# Open_Playback_Recorder_Bottom.net
KiCad netlist of a schematic drawn in EAGLE
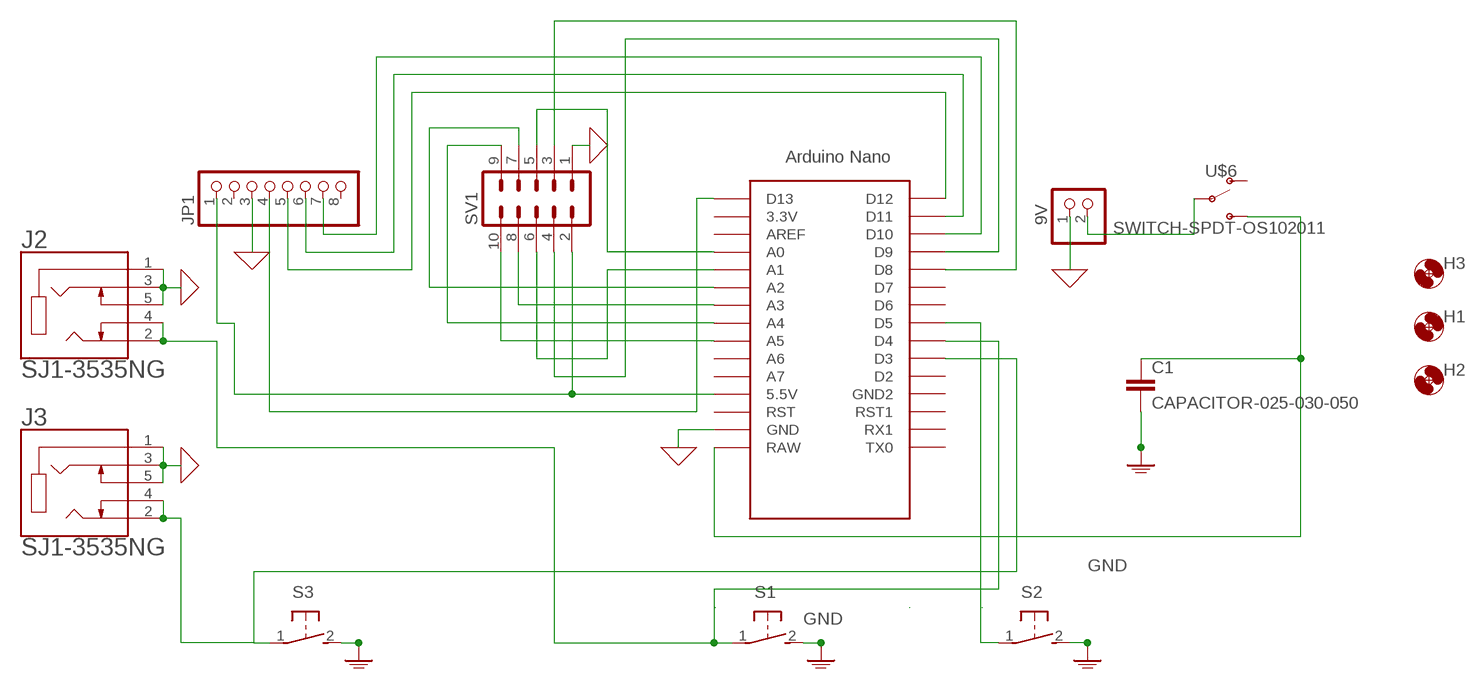
[diagram p0: schematic, sheet 1]

(export (version "E")
  (design (tool "Eeschema 10.0.6"))
  (components
    (comp (ref "9V")
      (value "PINHD-1X2")
      (footprint "eagle-import:1X02")
      (libsource (lib "eagle-import") (part "PINHD-1X2"))
    )
    (comp (ref "C1")
      (value "CAPACITOR-025-030-050")
      (footprint "eagle-import:CAP-025-030X050")
      (libsource (lib "eagle-import") (part "CAPACITOR-025-030-050"))
    )
    (comp (ref "H1")
      (value "MOUNT-HOLE-3MM-CLEAR")
      (footprint "eagle-import:HOLE-3MM-CLEAR")
      (libsource (lib "eagle-import") (part "MOUNT-HOLE-3MM-CLEAR"))
    )
    (comp (ref "H2")
      (value "MOUNT-HOLE-3MM-CLEAR")
      (footprint "eagle-import:HOLE-3MM-CLEAR")
      (libsource (lib "eagle-import") (part "MOUNT-HOLE-3MM-CLEAR"))
    )
    (comp (ref "H3")
      (value "MOUNT-HOLE-3MM-CLEAR")
      (footprint "eagle-import:HOLE-3MM-CLEAR")
      (libsource (lib "eagle-import") (part "MOUNT-HOLE-3MM-CLEAR"))
    )
    (comp (ref "J2")
      (value "SJ1-3535NG")
      (footprint "eagle-import:CUI_SJ1-3535NG")
      (fields (field (name "MANUFACTURER") "CUI"))
      (libsource (lib "eagle-import") (part "SJ1-3535NG"))
    )
    (comp (ref "J3")
      (value "SJ1-3535NG")
      (footprint "eagle-import:CUI_SJ1-3535NG")
      (fields (field (name "MANUFACTURER") "CUI"))
      (libsource (lib "eagle-import") (part "SJ1-3535NG"))
    )
    (comp (ref "JP1")
      (value "HEADER_MALE-1X8ROUND")
      (footprint "eagle-import:1X08_ROUND")
      (libsource (lib "eagle-import") (part "HEADER_MALE-1X8ROUND"))
    )
    (comp (ref "S1")
      (value "SWITCH_OMRON_RA-RA")
      (footprint "eagle-import:B3F-31XX")
      (libsource (lib "eagle-import") (part "SWITCH_OMRON_RA-RA"))
    )
    (comp (ref "S2")
      (value "SWITCH_OMRON_RA-RA")
      (footprint "eagle-import:B3F-31XX")
      (libsource (lib "eagle-import") (part "SWITCH_OMRON_RA-RA"))
    )
    (comp (ref "S3")
      (value "SWITCH_OMRON_RA-RA")
      (footprint "eagle-import:B3F-31XX")
      (libsource (lib "eagle-import") (part "SWITCH_OMRON_RA-RA"))
    )
    (comp (ref "SV1")
      (value "MA05-2")
      (footprint "eagle-import:MA05-2")
      (libsource (lib "eagle-import") (part "MA05-2"))
    )
    (comp (ref "U$1")
      (value "NANO")
      (footprint "eagle-import:NANO")
      (libsource (lib "eagle-import") (part "NANO"))
    )
    (comp (ref "U$6")
      (value "SWITCH-SPDT-OS102011")
      (footprint "eagle-import:SWITCH_SPDT_11MA1QS1")
      (libsource (lib "eagle-import") (part "SWITCH-SPDT-OS102011"))
    )
  )
  (nets
    (net (code "1") (name "GND") (class "Default")
      (node (ref "9V") (pin "1") (pinfunction "1_1") (pintype "passive"))
      (node (ref "J2") (pin "1") (pinfunction "1_1") (pintype "passive"))
      (node (ref "J2") (pin "3") (pinfunction "3_3") (pintype "passive"))
      (node (ref "J2") (pin "5") (pinfunction "5_5") (pintype "passive"))
      (node (ref "J3") (pin "1") (pinfunction "1_1") (pintype "passive"))
      (node (ref "J3") (pin "3") (pinfunction "3_3") (pintype "passive"))
      (node (ref "J3") (pin "5") (pinfunction "5_5") (pintype "passive"))
      (node (ref "JP1") (pin "3") (pinfunction "3_3") (pintype "passive"))
      (node (ref "S1") (pin "2") (pinfunction "2_2") (pintype "passive"))
      (node (ref "S2") (pin "2") (pinfunction "2_2") (pintype "passive"))
      (node (ref "S3") (pin "2") (pinfunction "2_2") (pintype "passive"))
      (node (ref "SV1") (pin "1") (pinfunction "1_1") (pintype "passive"))
      (node (ref "U$1") (pin "GND") (pinfunction "GND_GND") (pintype "bidirectional"))
    )
    (net (code "2") (name "Net-(C1-Pad2)") (class "Default")
      (node (ref "C1") (pin "2") (pinfunction "2_2") (pintype "passive"))
    )
    (net (code "3") (name "Net-(J2-Pad2)") (class "Default")
      (node (ref "J2") (pin "2") (pinfunction "2_2") (pintype "passive"))
      (node (ref "J2") (pin "4") (pinfunction "4_4") (pintype "passive"))
      (node (ref "S1") (pin "1") (pinfunction "1_1") (pintype "passive"))
      (node (ref "U$1") (pin "D4") (pinfunction "D4_D4") (pintype "bidirectional"))
    )
    (net (code "4") (name "Net-(J3-Pad2)") (class "Default")
      (node (ref "J3") (pin "2") (pinfunction "2_2") (pintype "passive"))
      (node (ref "J3") (pin "4") (pinfunction "4_4") (pintype "passive"))
      (node (ref "S3") (pin "1") (pinfunction "1_1") (pintype "passive"))
      (node (ref "U$1") (pin "D3") (pinfunction "D3_D3") (pintype "bidirectional"))
    )
    (net (code "5") (name "Net-(JP1-Pad4)") (class "Default")
      (node (ref "JP1") (pin "4") (pinfunction "4_4") (pintype "passive"))
      (node (ref "U$1") (pin "D13") (pinfunction "D13_D13") (pintype "bidirectional"))
    )
    (net (code "6") (name "Net-(JP1-Pad5)") (class "Default")
      (node (ref "JP1") (pin "5") (pinfunction "5_5") (pintype "passive"))
      (node (ref "U$1") (pin "D12") (pinfunction "D12_D12") (pintype "bidirectional"))
    )
    (net (code "7") (name "Net-(JP1-Pad6)") (class "Default")
      (node (ref "JP1") (pin "6") (pinfunction "6_6") (pintype "passive"))
      (node (ref "U$1") (pin "D11") (pinfunction "D11_D11") (pintype "bidirectional"))
    )
    (net (code "8") (name "Net-(JP1-Pad7)") (class "Default")
      (node (ref "JP1") (pin "7") (pinfunction "7_7") (pintype "passive"))
      (node (ref "U$1") (pin "D10") (pinfunction "D10_D10") (pintype "bidirectional"))
    )
    (net (code "9") (name "Net-(S2-Pad1)") (class "Default")
      (node (ref "S2") (pin "1") (pinfunction "1_1") (pintype "passive"))
      (node (ref "U$1") (pin "D5") (pinfunction "D5_D5") (pintype "bidirectional"))
    )
    (net (code "10") (name "Net-(SV1-Pad3)") (class "Default")
      (node (ref "SV1") (pin "3") (pinfunction "3_3") (pintype "passive"))
      (node (ref "U$1") (pin "D8") (pinfunction "D8_D8") (pintype "bidirectional"))
    )
    (net (code "11") (name "Net-(SV1-Pad4)") (class "Default")
      (node (ref "SV1") (pin "4") (pinfunction "4_4") (pintype "passive"))
      (node (ref "U$1") (pin "D9") (pinfunction "D9_D9") (pintype "bidirectional"))
    )
    (net (code "12") (name "Net-(SV1-Pad5)") (class "Default")
      (node (ref "SV1") (pin "5") (pinfunction "5_5") (pintype "passive"))
      (node (ref "U$1") (pin "A0") (pinfunction "A0_A0") (pintype "bidirectional"))
    )
    (net (code "13") (name "Net-(SV1-Pad6)") (class "Default")
      (node (ref "SV1") (pin "6") (pinfunction "6_6") (pintype "passive"))
      (node (ref "U$1") (pin "A1") (pinfunction "A1_A1") (pintype "bidirectional"))
    )
    (net (code "14") (name "Net-(SV1-Pad7)") (class "Default")
      (node (ref "SV1") (pin "7") (pinfunction "7_7") (pintype "passive"))
      (node (ref "U$1") (pin "A2") (pinfunction "A2_A2") (pintype "bidirectional"))
    )
    (net (code "15") (name "Net-(SV1-Pad8)") (class "Default")
      (node (ref "SV1") (pin "8") (pinfunction "8_8") (pintype "passive"))
      (node (ref "U$1") (pin "A3") (pinfunction "A3_A3") (pintype "bidirectional"))
    )
    (net (code "16") (name "Net-(SV1-Pad9)") (class "Default")
      (node (ref "SV1") (pin "9") (pinfunction "9_9") (pintype "passive"))
      (node (ref "U$1") (pin "A4") (pinfunction "A4_A4") (pintype "bidirectional"))
    )
    (net (code "17") (name "Net-(SV1-Pad10)") (class "Default")
      (node (ref "SV1") (pin "10") (pinfunction "10_10") (pintype "passive"))
      (node (ref "U$1") (pin "A5") (pinfunction "A5_A5") (pintype "bidirectional"))
    )
    (net (code "18") (name "Net-(U$1-5.5V)") (class "Default")
      (node (ref "JP1") (pin "1") (pinfunction "1_1") (pintype "passive"))
      (node (ref "SV1") (pin "2") (pinfunction "2_2") (pintype "passive"))
      (node (ref "U$1") (pin "5V") (pinfunction "5.5V_5V") (pintype "bidirectional"))
    )
    (net (code "19") (name "Net-(U$6-P)") (class "Default")
      (node (ref "9V") (pin "2") (pinfunction "2_2") (pintype "passive"))
      (node (ref "U$6") (pin "2") (pinfunction "P_2") (pintype "passive"))
    )
    (net (code "20") (name "Net-(U$6-S)") (class "Default")
      (node (ref "C1") (pin "1") (pinfunction "1_1") (pintype "passive"))
      (node (ref "U$1") (pin "RAW") (pinfunction "RAW_RAW") (pintype "bidirectional"))
      (node (ref "U$6") (pin "3") (pinfunction "S_3") (pintype "passive"))
    )
    (net (code "21") (name "unconnected-(JP1-Pad2)") (class "Default")
      (node (ref "JP1") (pin "2") (pinfunction "2_2") (pintype "passive"))
    )
    (net (code "22") (name "unconnected-(JP1-Pad8)") (class "Default")
      (node (ref "JP1") (pin "8") (pinfunction "8_8") (pintype "passive"))
    )
    (net (code "23") (name "unconnected-(U$1-GND2-PadGND1)") (class "Default")
      (node (ref "U$1") (pin "GND1") (pinfunction "GND2_GND1") (pintype "bidirectional"))
    )
    (net (code "24") (name "unconnected-(U$1-Pad3.3V)") (class "Default")
      (node (ref "U$1") (pin "3.3V") (pinfunction "3.3V_3.3V") (pintype "bidirectional"))
    )
    (net (code "25") (name "unconnected-(U$1-PadA6)") (class "Default")
      (node (ref "U$1") (pin "A6") (pinfunction "A6_A6") (pintype "bidirectional"))
    )
    (net (code "26") (name "unconnected-(U$1-PadA7)") (class "Default")
      (node (ref "U$1") (pin "A7") (pinfunction "A7_A7") (pintype "bidirectional"))
    )
    (net (code "27") (name "unconnected-(U$1-PadAREF)") (class "Default")
      (node (ref "U$1") (pin "AREF") (pinfunction "AREF_AREF") (pintype "bidirectional"))
    )
    (net (code "28") (name "unconnected-(U$1-PadD2)") (class "Default")
      (node (ref "U$1") (pin "D2") (pinfunction "D2_D2") (pintype "bidirectional"))
    )
    (net (code "29") (name "unconnected-(U$1-PadD6)") (class "Default")
      (node (ref "U$1") (pin "D6") (pinfunction "D6_D6") (pintype "bidirectional"))
    )
    (net (code "30") (name "unconnected-(U$1-PadD7)") (class "Default")
      (node (ref "U$1") (pin "D7") (pinfunction "D7_D7") (pintype "bidirectional"))
    )
    (net (code "31") (name "unconnected-(U$1-PadICSP1)") (class "Default")
      (node (ref "U$1") (pin "ICSP1") (pinfunction "ICSP1_ICSP1") (pintype "bidirectional"))
    )
    (net (code "32") (name "unconnected-(U$1-PadICSP2)") (class "Default")
      (node (ref "U$1") (pin "ICSP2") (pinfunction "ICSP2_ICSP2") (pintype "bidirectional"))
    )
    (net (code "33") (name "unconnected-(U$1-PadICSP3)") (class "Default")
      (node (ref "U$1") (pin "ICSP3") (pinfunction "ICSP3_ICSP3") (pintype "bidirectional"))
    )
    (net (code "34") (name "unconnected-(U$1-PadICSP4)") (class "Default")
      (node (ref "U$1") (pin "ICSP4") (pinfunction "ICSP4_ICSP4") (pintype "bidirectional"))
    )
    (net (code "35") (name "unconnected-(U$1-PadICSP5)") (class "Default")
      (node (ref "U$1") (pin "ICSP5") (pinfunction "ICSP5_ICSP5") (pintype "bidirectional"))
    )
    (net (code "36") (name "unconnected-(U$1-PadICSP6)") (class "Default")
      (node (ref "U$1") (pin "ICSP6") (pinfunction "ICSP6_ICSP6") (pintype "bidirectional"))
    )
    (net (code "37") (name "unconnected-(U$1-PadRST)") (class "Default")
      (node (ref "U$1") (pin "RST") (pinfunction "RST_RST") (pintype "bidirectional"))
    )
    (net (code "38") (name "unconnected-(U$1-PadRST1)") (class "Default")
      (node (ref "U$1") (pin "RST1") (pinfunction "RST1_RST1") (pintype "bidirectional"))
    )
    (net (code "39") (name "unconnected-(U$1-PadRX1)") (class "Default")
      (node (ref "U$1") (pin "RX1") (pinfunction "RX1_RX1") (pintype "bidirectional"))
    )
    (net (code "40") (name "unconnected-(U$1-PadTX0)") (class "Default")
      (node (ref "U$1") (pin "TX0") (pinfunction "TX0_TX0") (pintype "bidirectional"))
    )
    (net (code "41") (name "unconnected-(U$6-O-Pad1)") (class "Default")
      (node (ref "U$6") (pin "1") (pinfunction "O_1") (pintype "passive"))
    )
  )
)
